# PCA9685.net
KiCad netlist of a schematic drawn in Altium Designer
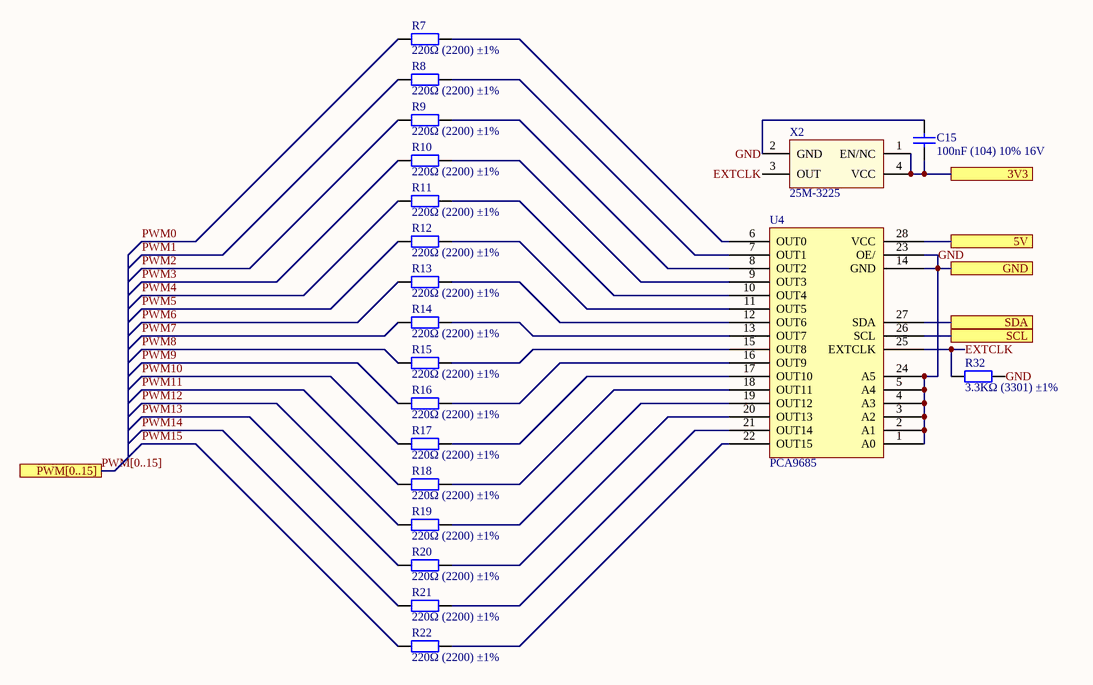
[diagram p0: PCA9685.SchDoc]

(export (version "E")
  (design (tool "Eeschema 10.0.6"))
  (components
    (comp (ref "C15")
      (value "100nF (104) 10% 16V")
      (footprint "0402_C")
      (description "贴片电容")
      (libsource (lib "Miscellaneous Devices LC") (part "0402 100nF (104) 10% 16V"))
    )
    (comp (ref "R7")
      (value "220Ω (2200) ±1%")
      (footprint "0402_R")
      (description "贴片电阻")
      (libsource (lib "Miscellaneous Devices LC") (part "0402 220Ω (2200) 1%"))
    )
    (comp (ref "R8")
      (value "220Ω (2200) ±1%")
      (footprint "0402_R")
      (description "贴片电阻")
      (libsource (lib "Miscellaneous Devices LC") (part "0402 220Ω (2200) 1%"))
    )
    (comp (ref "R9")
      (value "220Ω (2200) ±1%")
      (footprint "0402_R")
      (description "贴片电阻")
      (libsource (lib "Miscellaneous Devices LC") (part "0402 220Ω (2200) 1%"))
    )
    (comp (ref "R10")
      (value "220Ω (2200) ±1%")
      (footprint "0402_R")
      (description "贴片电阻")
      (libsource (lib "Miscellaneous Devices LC") (part "0402 220Ω (2200) 1%"))
    )
    (comp (ref "R11")
      (value "220Ω (2200) ±1%")
      (footprint "0402_R")
      (description "贴片电阻")
      (libsource (lib "Miscellaneous Devices LC") (part "0402 220Ω (2200) 1%"))
    )
    (comp (ref "R12")
      (value "220Ω (2200) ±1%")
      (footprint "0402_R")
      (description "贴片电阻")
      (libsource (lib "Miscellaneous Devices LC") (part "0402 220Ω (2200) 1%"))
    )
    (comp (ref "R13")
      (value "220Ω (2200) ±1%")
      (footprint "0402_R")
      (description "贴片电阻")
      (libsource (lib "Miscellaneous Devices LC") (part "0402 220Ω (2200) 1%"))
    )
    (comp (ref "R14")
      (value "220Ω (2200) ±1%")
      (footprint "0402_R")
      (description "贴片电阻")
      (libsource (lib "Miscellaneous Devices LC") (part "0402 220Ω (2200) 1%"))
    )
    (comp (ref "R15")
      (value "220Ω (2200) ±1%")
      (footprint "0402_R")
      (description "贴片电阻")
      (libsource (lib "Miscellaneous Devices LC") (part "0402 220Ω (2200) 1%"))
    )
    (comp (ref "R16")
      (value "220Ω (2200) ±1%")
      (footprint "0402_R")
      (description "贴片电阻")
      (libsource (lib "Miscellaneous Devices LC") (part "0402 220Ω (2200) 1%"))
    )
    (comp (ref "R17")
      (value "220Ω (2200) ±1%")
      (footprint "0402_R")
      (description "贴片电阻")
      (libsource (lib "Miscellaneous Devices LC") (part "0402 220Ω (2200) 1%"))
    )
    (comp (ref "R18")
      (value "220Ω (2200) ±1%")
      (footprint "0402_R")
      (description "贴片电阻")
      (libsource (lib "Miscellaneous Devices LC") (part "0402 220Ω (2200) 1%"))
    )
    (comp (ref "R19")
      (value "220Ω (2200) ±1%")
      (footprint "0402_R")
      (description "贴片电阻")
      (libsource (lib "Miscellaneous Devices LC") (part "0402 220Ω (2200) 1%"))
    )
    (comp (ref "R20")
      (value "220Ω (2200) ±1%")
      (footprint "0402_R")
      (description "贴片电阻")
      (libsource (lib "Miscellaneous Devices LC") (part "0402 220Ω (2200) 1%"))
    )
    (comp (ref "R21")
      (value "220Ω (2200) ±1%")
      (footprint "0402_R")
      (description "贴片电阻")
      (libsource (lib "Miscellaneous Devices LC") (part "0402 220Ω (2200) 1%"))
    )
    (comp (ref "R22")
      (value "220Ω (2200) ±1%")
      (footprint "0402_R")
      (description "贴片电阻")
      (libsource (lib "Miscellaneous Devices LC") (part "0402 220Ω (2200) 1%"))
    )
    (comp (ref "R32")
      (value "3.3KΩ (3301) ±1%")
      (footprint "0402_R")
      (description "贴片电阻")
      (libsource (lib "Miscellaneous Devices LC") (part "0402 3.3KΩ (3301) 1%"))
    )
    (comp (ref "U4")
      (value "PCA9685")
      (footprint "TSSOP28_M")
      (description "16-channel, 12-bit PWM Fm+ I2C-bus LED controller")
      (libsource (lib "Custom Library") (part "PCA9685"))
    )
    (comp (ref "X2")
      (value "25M-3225")
      (footprint "OSC 3225-4P")
      (description "4脚有源晶振")
      (fields (field (name "版权归属") "源创客"))
      (libsource (lib "10.1 - 保险丝-晶振") (part "XTAL-ACT-4P"))
    )
  )
  (nets
    (net (code "1") (name "/3V3") (class "Default")
      (node (ref "C15") (pin "1") (pinfunction "1_1") (pintype "passive"))
      (node (ref "X2") (pin "1") (pinfunction "EN/NC_1") (pintype "passive"))
      (node (ref "X2") (pin "4") (pinfunction "VCC_4") (pintype "passive"))
    )
    (net (code "2") (name "/5V") (class "Default")
      (node (ref "U4") (pin "28") (pinfunction "VCC_28") (pintype "passive"))
    )
    (net (code "3") (name "/EXTCLK") (class "Default")
      (node (ref "R32") (pin "1") (pinfunction "1_1") (pintype "passive"))
      (node (ref "U4") (pin "25") (pinfunction "EXTCLK_25") (pintype "passive"))
      (node (ref "X2") (pin "3") (pinfunction "OUT_3") (pintype "passive"))
    )
    (net (code "4") (name "/GND") (class "Default")
      (node (ref "C15") (pin "2") (pinfunction "2_2") (pintype "passive"))
      (node (ref "R32") (pin "2") (pinfunction "2_2") (pintype "passive"))
      (node (ref "U4") (pin "1") (pinfunction "A0_1") (pintype "passive"))
      (node (ref "U4") (pin "14") (pinfunction "GND_14") (pintype "passive"))
      (node (ref "U4") (pin "2") (pinfunction "A1_2") (pintype "passive"))
      (node (ref "U4") (pin "23") (pinfunction "OE/_23") (pintype "passive"))
      (node (ref "U4") (pin "24") (pinfunction "A5_24") (pintype "passive"))
      (node (ref "U4") (pin "3") (pinfunction "A2_3") (pintype "passive"))
      (node (ref "U4") (pin "4") (pinfunction "A3_4") (pintype "passive"))
      (node (ref "U4") (pin "5") (pinfunction "A4_5") (pintype "passive"))
      (node (ref "X2") (pin "2") (pinfunction "GND_2") (pintype "passive"))
    )
    (net (code "5") (name "/PWM0") (class "Default")
      (node (ref "R7") (pin "1") (pinfunction "1_1") (pintype "passive"))
    )
    (net (code "6") (name "/PWM1") (class "Default")
      (node (ref "R8") (pin "1") (pinfunction "1_1") (pintype "passive"))
    )
    (net (code "7") (name "/PWM2") (class "Default")
      (node (ref "R9") (pin "1") (pinfunction "1_1") (pintype "passive"))
    )
    (net (code "8") (name "/PWM3") (class "Default")
      (node (ref "R10") (pin "1") (pinfunction "1_1") (pintype "passive"))
    )
    (net (code "9") (name "/PWM4") (class "Default")
      (node (ref "R11") (pin "1") (pinfunction "1_1") (pintype "passive"))
    )
    (net (code "10") (name "/PWM5") (class "Default")
      (node (ref "R12") (pin "1") (pinfunction "1_1") (pintype "passive"))
    )
    (net (code "11") (name "/PWM6") (class "Default")
      (node (ref "R13") (pin "1") (pinfunction "1_1") (pintype "passive"))
    )
    (net (code "12") (name "/PWM7") (class "Default")
      (node (ref "R14") (pin "1") (pinfunction "1_1") (pintype "passive"))
    )
    (net (code "13") (name "/PWM8") (class "Default")
      (node (ref "R15") (pin "1") (pinfunction "1_1") (pintype "passive"))
    )
    (net (code "14") (name "/PWM9") (class "Default")
      (node (ref "R16") (pin "1") (pinfunction "1_1") (pintype "passive"))
    )
    (net (code "15") (name "/PWM10") (class "Default")
      (node (ref "R17") (pin "1") (pinfunction "1_1") (pintype "passive"))
    )
    (net (code "16") (name "/PWM11") (class "Default")
      (node (ref "R18") (pin "1") (pinfunction "1_1") (pintype "passive"))
    )
    (net (code "17") (name "/PWM12") (class "Default")
      (node (ref "R19") (pin "1") (pinfunction "1_1") (pintype "passive"))
    )
    (net (code "18") (name "/PWM13") (class "Default")
      (node (ref "R20") (pin "1") (pinfunction "1_1") (pintype "passive"))
    )
    (net (code "19") (name "/PWM14") (class "Default")
      (node (ref "R21") (pin "1") (pinfunction "1_1") (pintype "passive"))
    )
    (net (code "20") (name "/PWM15") (class "Default")
      (node (ref "R22") (pin "1") (pinfunction "1_1") (pintype "passive"))
    )
    (net (code "22") (name "/SCL") (class "Default")
      (node (ref "U4") (pin "26") (pinfunction "SCL_26") (pintype "passive"))
    )
    (net (code "23") (name "/SDA") (class "Default")
      (node (ref "U4") (pin "27") (pinfunction "SDA_27") (pintype "passive"))
    )
    (net (code "24") (name "Net-(U4-OUT0)") (class "Default")
      (node (ref "R7") (pin "2") (pinfunction "2_2") (pintype "passive"))
      (node (ref "U4") (pin "6") (pinfunction "OUT0_6") (pintype "passive"))
    )
    (net (code "25") (name "Net-(U4-OUT1)") (class "Default")
      (node (ref "R8") (pin "2") (pinfunction "2_2") (pintype "passive"))
      (node (ref "U4") (pin "7") (pinfunction "OUT1_7") (pintype "passive"))
    )
    (net (code "26") (name "Net-(U4-OUT2)") (class "Default")
      (node (ref "R9") (pin "2") (pinfunction "2_2") (pintype "passive"))
      (node (ref "U4") (pin "8") (pinfunction "OUT2_8") (pintype "passive"))
    )
    (net (code "27") (name "Net-(U4-OUT3)") (class "Default")
      (node (ref "R10") (pin "2") (pinfunction "2_2") (pintype "passive"))
      (node (ref "U4") (pin "9") (pinfunction "OUT3_9") (pintype "passive"))
    )
    (net (code "28") (name "Net-(U4-OUT4)") (class "Default")
      (node (ref "R11") (pin "2") (pinfunction "2_2") (pintype "passive"))
      (node (ref "U4") (pin "10") (pinfunction "OUT4_10") (pintype "passive"))
    )
    (net (code "29") (name "Net-(U4-OUT5)") (class "Default")
      (node (ref "R12") (pin "2") (pinfunction "2_2") (pintype "passive"))
      (node (ref "U4") (pin "11") (pinfunction "OUT5_11") (pintype "passive"))
    )
    (net (code "30") (name "Net-(U4-OUT6)") (class "Default")
      (node (ref "R13") (pin "2") (pinfunction "2_2") (pintype "passive"))
      (node (ref "U4") (pin "12") (pinfunction "OUT6_12") (pintype "passive"))
    )
    (net (code "31") (name "Net-(U4-OUT7)") (class "Default")
      (node (ref "R14") (pin "2") (pinfunction "2_2") (pintype "passive"))
      (node (ref "U4") (pin "13") (pinfunction "OUT7_13") (pintype "passive"))
    )
    (net (code "32") (name "Net-(U4-OUT8)") (class "Default")
      (node (ref "R15") (pin "2") (pinfunction "2_2") (pintype "passive"))
      (node (ref "U4") (pin "15") (pinfunction "OUT8_15") (pintype "passive"))
    )
    (net (code "33") (name "Net-(U4-OUT9)") (class "Default")
      (node (ref "R16") (pin "2") (pinfunction "2_2") (pintype "passive"))
      (node (ref "U4") (pin "16") (pinfunction "OUT9_16") (pintype "passive"))
    )
    (net (code "34") (name "Net-(U4-OUT10)") (class "Default")
      (node (ref "R17") (pin "2") (pinfunction "2_2") (pintype "passive"))
      (node (ref "U4") (pin "17") (pinfunction "OUT10_17") (pintype "passive"))
    )
    (net (code "35") (name "Net-(U4-OUT11)") (class "Default")
      (node (ref "R18") (pin "2") (pinfunction "2_2") (pintype "passive"))
      (node (ref "U4") (pin "18") (pinfunction "OUT11_18") (pintype "passive"))
    )
    (net (code "36") (name "Net-(U4-OUT12)") (class "Default")
      (node (ref "R19") (pin "2") (pinfunction "2_2") (pintype "passive"))
      (node (ref "U4") (pin "19") (pinfunction "OUT12_19") (pintype "passive"))
    )
    (net (code "37") (name "Net-(U4-OUT13)") (class "Default")
      (node (ref "R20") (pin "2") (pinfunction "2_2") (pintype "passive"))
      (node (ref "U4") (pin "20") (pinfunction "OUT13_20") (pintype "passive"))
    )
    (net (code "38") (name "Net-(U4-OUT14)") (class "Default")
      (node (ref "R21") (pin "2") (pinfunction "2_2") (pintype "passive"))
      (node (ref "U4") (pin "21") (pinfunction "OUT14_21") (pintype "passive"))
    )
    (net (code "39") (name "Net-(U4-OUT15)") (class "Default")
      (node (ref "R22") (pin "2") (pinfunction "2_2") (pintype "passive"))
      (node (ref "U4") (pin "22") (pinfunction "OUT15_22") (pintype "passive"))
    )
  )
)
